# booster-pump-interlock.net
KiCad netlist of a schematic drawn in EAGLE
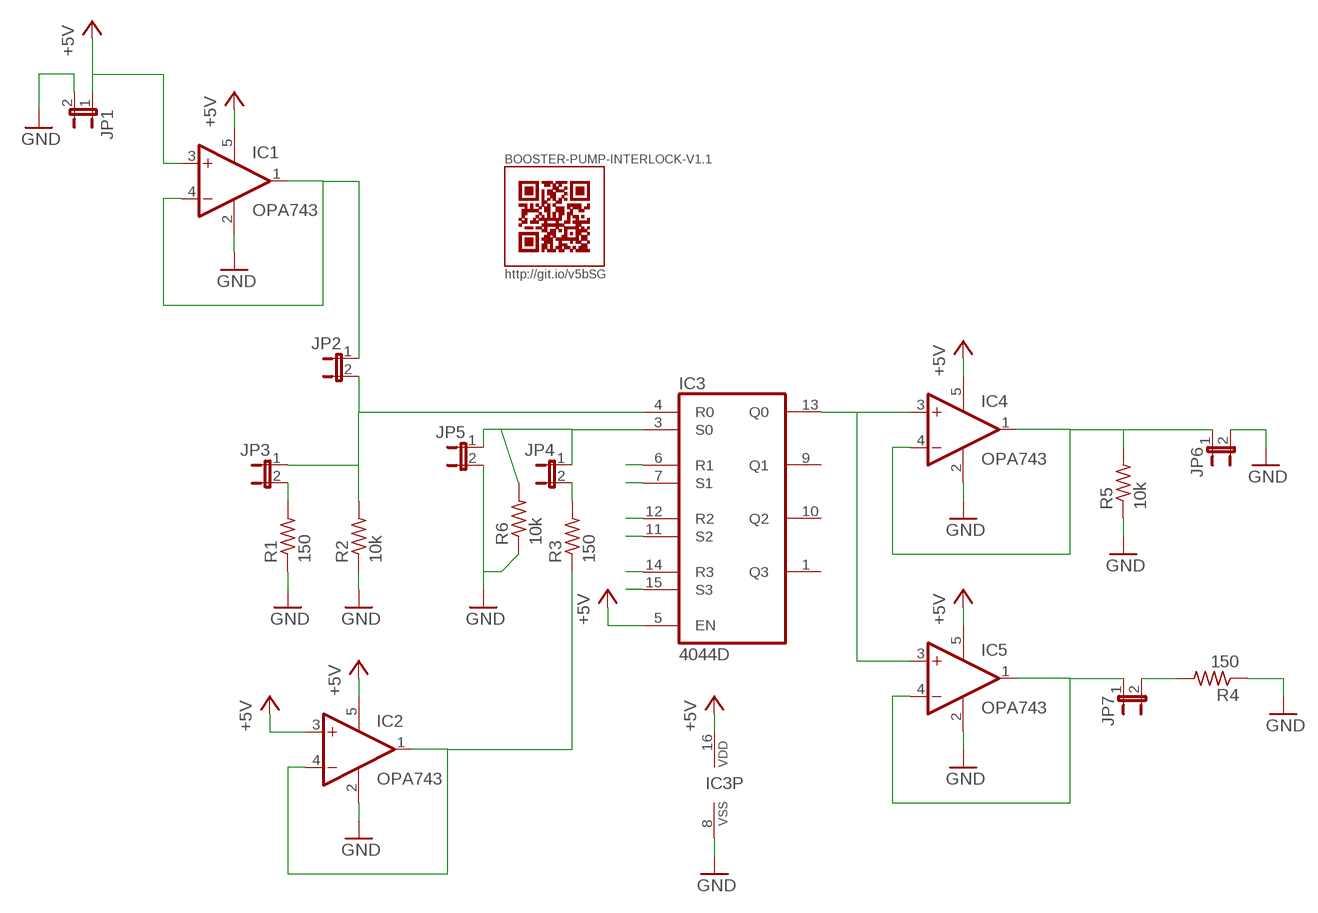
[diagram p0: schematic, sheet 1]

(export (version "E")
  (design (tool "Eeschema 10.0.6"))
  (components
    (comp (ref "BOOSTER-PUMP-INTERLOCK-V1.1")
      (value "QR-HTTP://GIT.IO/V5BSG-WIRE")
      (footprint "eagle-import:QR-HTTP___GIT.IO_V5BSG-WIRE")
      (libsource (lib "eagle-import") (part "QR-HTTP{colon}//GIT.IO/V5BSG-WIRE"))
    )
    (comp (ref "IC1")
      (value "OPA743")
      (footprint "eagle-import:SOT23-5")
      (fields (field (name "PARTNO") "OPA743NA/3KCT-ND"))
      (libsource (lib "eagle-import") (part "OPA743"))
    )
    (comp (ref "IC2")
      (value "OPA743")
      (footprint "eagle-import:SOT23-5")
      (fields (field (name "PARTNO") "OPA743NA/3KCT-ND"))
      (libsource (lib "eagle-import") (part "OPA743"))
    )
    (comp (ref "IC3")
      (value "4044D")
      (footprint "eagle-import:SO16")
      (libsource (lib "eagle-import") (part "4044D"))
    )
    (comp (ref "IC4")
      (value "OPA743")
      (footprint "eagle-import:SOT23-5")
      (fields (field (name "PARTNO") "OPA743NA/3KCT-ND"))
      (libsource (lib "eagle-import") (part "OPA743"))
    )
    (comp (ref "IC5")
      (value "OPA743")
      (footprint "eagle-import:SOT23-5")
      (fields (field (name "PARTNO") "OPA743NA/3KCT-ND"))
      (libsource (lib "eagle-import") (part "OPA743"))
    )
    (comp (ref "JP1")
      (value "JP1E")
      (footprint "eagle-import:JP1")
      (libsource (lib "eagle-import") (part "JP1E"))
    )
    (comp (ref "JP2")
      (value "JP1E")
      (footprint "eagle-import:JP1")
      (libsource (lib "eagle-import") (part "JP1E"))
    )
    (comp (ref "JP3")
      (value "JP1E")
      (footprint "eagle-import:JP1")
      (libsource (lib "eagle-import") (part "JP1E"))
    )
    (comp (ref "JP4")
      (value "JP1E")
      (footprint "eagle-import:JP1")
      (libsource (lib "eagle-import") (part "JP1E"))
    )
    (comp (ref "JP5")
      (value "JP1E")
      (footprint "eagle-import:JP1")
      (libsource (lib "eagle-import") (part "JP1E"))
    )
    (comp (ref "JP6")
      (value "JP1E")
      (footprint "eagle-import:JP1")
      (libsource (lib "eagle-import") (part "JP1E"))
    )
    (comp (ref "JP7")
      (value "JP1E")
      (footprint "eagle-import:JP1")
      (libsource (lib "eagle-import") (part "JP1E"))
    )
    (comp (ref "R1")
      (value "150")
      (footprint "eagle-import:R0805")
      (libsource (lib "eagle-import") (part "R-US_R0805"))
    )
    (comp (ref "R2")
      (value "10k")
      (footprint "eagle-import:R0805")
      (libsource (lib "eagle-import") (part "R-US_R0805"))
    )
    (comp (ref "R3")
      (value "150")
      (footprint "eagle-import:R0805")
      (libsource (lib "eagle-import") (part "R-US_R0805"))
    )
    (comp (ref "R4")
      (value "150")
      (footprint "eagle-import:R0805")
      (libsource (lib "eagle-import") (part "R-US_R0805"))
    )
    (comp (ref "R5")
      (value "10k")
      (footprint "eagle-import:R0805")
      (libsource (lib "eagle-import") (part "R-US_R0805"))
    )
    (comp (ref "R6")
      (value "10k")
      (footprint "eagle-import:M1206")
      (libsource (lib "eagle-import") (part "R-US_M1206"))
    )
  )
  (nets
    (net (code "1") (name "+5V") (class "Default")
      (node (ref "IC1") (pin "3") (pinfunction "+IN_3") (pintype "input"))
      (node (ref "IC1") (pin "5") (pinfunction "V+_5") (pintype "power_in"))
      (node (ref "IC2") (pin "3") (pinfunction "+IN_3") (pintype "input"))
      (node (ref "IC2") (pin "5") (pinfunction "V+_5") (pintype "power_in"))
      (node (ref "IC3") (pin "16") (pinfunction "VDD_16") (pintype "power_in"))
      (node (ref "IC3") (pin "5") (pinfunction "EN_5") (pintype "input"))
      (node (ref "IC4") (pin "5") (pinfunction "V+_5") (pintype "power_in"))
      (node (ref "IC5") (pin "5") (pinfunction "V+_5") (pintype "power_in"))
      (node (ref "JP1") (pin "1") (pinfunction "1_1") (pintype "passive"))
    )
    (net (code "2") (name "GND") (class "Default")
      (node (ref "IC1") (pin "2") (pinfunction "V-_2") (pintype "power_in"))
      (node (ref "IC2") (pin "2") (pinfunction "V-_2") (pintype "power_in"))
      (node (ref "IC3") (pin "11") (pinfunction "S2_11") (pintype "input"))
      (node (ref "IC3") (pin "12") (pinfunction "R2_12") (pintype "input"))
      (node (ref "IC3") (pin "14") (pinfunction "R3_14") (pintype "input"))
      (node (ref "IC3") (pin "15") (pinfunction "S3_15") (pintype "input"))
      (node (ref "IC3") (pin "6") (pinfunction "R1_6") (pintype "input"))
      (node (ref "IC3") (pin "7") (pinfunction "S1_7") (pintype "input"))
      (node (ref "IC3") (pin "8") (pinfunction "VSS_8") (pintype "power_in"))
      (node (ref "IC4") (pin "2") (pinfunction "V-_2") (pintype "power_in"))
      (node (ref "IC5") (pin "2") (pinfunction "V-_2") (pintype "power_in"))
      (node (ref "JP1") (pin "2") (pinfunction "2_2") (pintype "passive"))
      (node (ref "JP5") (pin "2") (pinfunction "2_2") (pintype "passive"))
      (node (ref "JP6") (pin "2") (pinfunction "2_2") (pintype "passive"))
      (node (ref "R1") (pin "1") (pinfunction "1_1") (pintype "passive"))
      (node (ref "R2") (pin "1") (pinfunction "1_1") (pintype "passive"))
      (node (ref "R4") (pin "1") (pinfunction "1_1") (pintype "passive"))
      (node (ref "R5") (pin "1") (pinfunction "1_1") (pintype "passive"))
      (node (ref "R6") (pin "1") (pinfunction "1_1") (pintype "passive"))
    )
    (net (code "3") (name "Net-(IC1--IN)") (class "Default")
      (node (ref "IC1") (pin "1") (pinfunction "OUT_1") (pintype "output"))
      (node (ref "IC1") (pin "4") (pinfunction "-IN_4") (pintype "input"))
      (node (ref "JP2") (pin "1") (pinfunction "1_1") (pintype "passive"))
    )
    (net (code "4") (name "Net-(IC2--IN)") (class "Default")
      (node (ref "IC2") (pin "1") (pinfunction "OUT_1") (pintype "output"))
      (node (ref "IC2") (pin "4") (pinfunction "-IN_4") (pintype "input"))
      (node (ref "R3") (pin "1") (pinfunction "1_1") (pintype "passive"))
    )
    (net (code "5") (name "Net-(IC3A-Q0)") (class "Default")
      (node (ref "IC3") (pin "13") (pinfunction "Q0_13") (pintype "output"))
      (node (ref "IC4") (pin "3") (pinfunction "+IN_3") (pintype "input"))
      (node (ref "IC5") (pin "3") (pinfunction "+IN_3") (pintype "input"))
    )
    (net (code "6") (name "Net-(IC3A-R0)") (class "Default")
      (node (ref "IC3") (pin "4") (pinfunction "R0_4") (pintype "input"))
      (node (ref "JP2") (pin "2") (pinfunction "2_2") (pintype "passive"))
      (node (ref "JP3") (pin "1") (pinfunction "1_1") (pintype "passive"))
      (node (ref "R2") (pin "2") (pinfunction "2_2") (pintype "passive"))
    )
    (net (code "7") (name "Net-(IC3A-S0)") (class "Default")
      (node (ref "IC3") (pin "3") (pinfunction "S0_3") (pintype "input"))
      (node (ref "JP4") (pin "1") (pinfunction "1_1") (pintype "passive"))
      (node (ref "JP5") (pin "1") (pinfunction "1_1") (pintype "passive"))
      (node (ref "R6") (pin "2") (pinfunction "2_2") (pintype "passive"))
    )
    (net (code "8") (name "Net-(IC4--IN)") (class "Default")
      (node (ref "IC4") (pin "1") (pinfunction "OUT_1") (pintype "output"))
      (node (ref "IC4") (pin "4") (pinfunction "-IN_4") (pintype "input"))
      (node (ref "JP6") (pin "1") (pinfunction "1_1") (pintype "passive"))
      (node (ref "R5") (pin "2") (pinfunction "2_2") (pintype "passive"))
    )
    (net (code "9") (name "Net-(IC5--IN)") (class "Default")
      (node (ref "IC5") (pin "1") (pinfunction "OUT_1") (pintype "output"))
      (node (ref "IC5") (pin "4") (pinfunction "-IN_4") (pintype "input"))
      (node (ref "JP7") (pin "1") (pinfunction "1_1") (pintype "passive"))
    )
    (net (code "10") (name "Net-(JP3-Pad2)") (class "Default")
      (node (ref "JP3") (pin "2") (pinfunction "2_2") (pintype "passive"))
      (node (ref "R1") (pin "2") (pinfunction "2_2") (pintype "passive"))
    )
    (net (code "11") (name "Net-(JP4-Pad2)") (class "Default")
      (node (ref "JP4") (pin "2") (pinfunction "2_2") (pintype "passive"))
      (node (ref "R3") (pin "2") (pinfunction "2_2") (pintype "passive"))
    )
    (net (code "12") (name "Net-(JP7-Pad2)") (class "Default")
      (node (ref "JP7") (pin "2") (pinfunction "2_2") (pintype "passive"))
      (node (ref "R4") (pin "2") (pinfunction "2_2") (pintype "passive"))
    )
    (net (code "13") (name "unconnected-(IC3A-Q1-Pad9)") (class "Default")
      (node (ref "IC3") (pin "9") (pinfunction "Q1_9") (pintype "output"))
    )
    (net (code "14") (name "unconnected-(IC3A-Q2-Pad10)") (class "Default")
      (node (ref "IC3") (pin "10") (pinfunction "Q2_10") (pintype "output"))
    )
    (net (code "15") (name "unconnected-(IC3A-Q3-Pad1)") (class "Default")
      (node (ref "IC3") (pin "1") (pinfunction "Q3_1") (pintype "output"))
    )
  )
)
